# Upstream_Port.net
KiCad netlist of a schematic drawn in Altium Designer
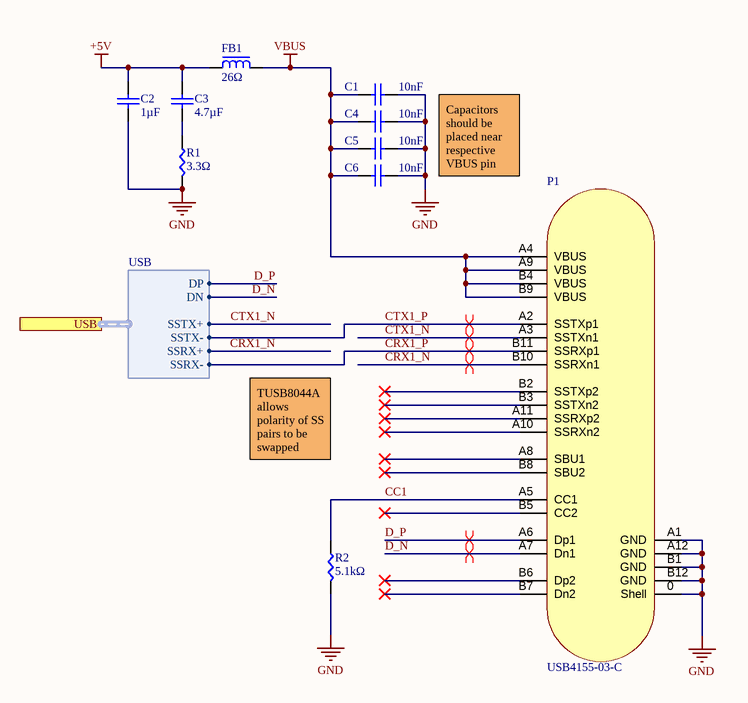
[diagram p0: Upstream_Port.SchDoc]

(export (version "E")
  (design (tool "Eeschema 10.0.6"))
  (components
    (comp (ref "C1")
      (value "10nF")
      (footprint "CAP0402")
      (description "10000 pF ±10% 50V Ceramic Capacitor X7R 0402 (1005 Metric)")
      (fields (field (name "VOLTAGE") "50V") (field (name "Comment") "CC0402KRX7R9BB103"))
      (libsource (lib "Schlib1") (part "CC0402KRX7R9BB103"))
    )
    (comp (ref "C2")
      (value "1µF")
      (footprint "CAP0402")
      (description "1 µF ±10% 50V Ceramic Capacitor X5R 0402 (1005 Metric)")
      (fields (field (name "VOLTAGE") "50V") (field (name "Comment") "GRM155R61H105KE05D"))
      (libsource (lib "Schlib1") (part "GRM155R61H105KE05D"))
    )
    (comp (ref "C3")
      (value "4.7µF")
      (footprint "CAP0603")
      (description "4.7 µF ±10% 25V Ceramic Capacitor X5R 0603 (1608 Metric)")
      (fields (field (name "VOLTAGE") "25V") (field (name "Comment") "GRM188R61E475KE11D"))
      (libsource (lib "Schlib1") (part "GRM188R61E475KE11D"))
    )
    (comp (ref "C4")
      (value "10nF")
      (footprint "CAP0402")
      (description "10000 pF ±10% 50V Ceramic Capacitor X7R 0402 (1005 Metric)")
      (fields (field (name "VOLTAGE") "50V") (field (name "Comment") "CC0402KRX7R9BB103"))
      (libsource (lib "Schlib1") (part "CC0402KRX7R9BB103"))
    )
    (comp (ref "C5")
      (value "10nF")
      (footprint "CAP0402")
      (description "10000 pF ±10% 50V Ceramic Capacitor X7R 0402 (1005 Metric)")
      (fields (field (name "VOLTAGE") "50V") (field (name "Comment") "CC0402KRX7R9BB103"))
      (libsource (lib "Schlib1") (part "CC0402KRX7R9BB103"))
    )
    (comp (ref "C6")
      (value "10nF")
      (footprint "CAP0402")
      (description "10000 pF ±10% 50V Ceramic Capacitor X7R 0402 (1005 Metric)")
      (fields (field (name "VOLTAGE") "50V") (field (name "Comment") "CC0402KRX7R9BB103"))
      (libsource (lib "Schlib1") (part "CC0402KRX7R9BB103"))
    )
    (comp (ref "FB1")
      (value "26Ω")
      (footprint "BLM18SG260TN1D")
      (description "26 Ohms @ 100 MHz 1 Power Line Ferrite Bead 0603 (1608 Metric) 6A 7mOhm")
      (fields (field (name "Comment") "BLM18SG260TN1D"))
      (libsource (lib "Schlib1") (part "BLM18SG260TN1D"))
    )
    (comp (ref "P1")
      (value "USB4155-03-C")
      (footprint "USB4155-03-C")
      (fields (field (name "MANUFACTURER") "GCT") (field (name "VOLTAGE") "48VDC"))
      (libsource (lib "Schlib1") (part "USB4155-03-C"))
    )
    (comp (ref "R1")
      (value "3.3Ω")
      (footprint "RES0402")
      (fields (field (name "Comment") "ESR10EZPJ3R3"))
      (libsource (lib "Schlib1") (part "ESR10EZPJ3R3"))
    )
    (comp (ref "R2")
      (value "5.1kΩ")
      (footprint "RES0402")
      (description "5.1 kOhms ±1% 0.063W, 1/16W Chip Resistor 0402 (1005 Metric) Moisture Resistant Thick Film")
      (fields (field (name "Comment") "RC0402FR-075K1L"))
      (libsource (lib "Schlib1") (part "RC0402FR-075K1L"))
    )
  )
  (nets
    (net (code "2") (name "+5V") (class "Default")
      (node (ref "C2") (pin "2") (pinfunction "2_2") (pintype "passive"))
      (node (ref "C3") (pin "2") (pinfunction "2_2") (pintype "passive"))
      (node (ref "FB1") (pin "1") (pinfunction "1_1") (pintype "passive"))
    )
    (net (code "3") (name "/CC1") (class "Default")
      (node (ref "P1") (pin "A5") (pinfunction "CC1_A5") (pintype "passive"))
      (node (ref "R2") (pin "2") (pinfunction "2_2") (pintype "passive"))
    )
    (net (code "4") (name "/CRX1_N") (class "Default")
      (node (ref "P1") (pin "B10") (pinfunction "SSRXn1_B10") (pintype "passive"))
    )
    (net (code "5") (name "/CRX1_P") (class "Default")
      (node (ref "P1") (pin "B11") (pinfunction "SSRXp1_B11") (pintype "passive"))
    )
    (net (code "6") (name "/CTX1_N") (class "Default")
      (node (ref "P1") (pin "A3") (pinfunction "SSTXn1_A3") (pintype "passive"))
    )
    (net (code "7") (name "/CTX1_P") (class "Default")
      (node (ref "P1") (pin "A2") (pinfunction "SSTXp1_A2") (pintype "passive"))
    )
    (net (code "8") (name "/D_N") (class "Default")
      (node (ref "P1") (pin "A7") (pinfunction "Dn1_A7") (pintype "passive"))
    )
    (net (code "9") (name "/D_P") (class "Default")
      (node (ref "P1") (pin "A6") (pinfunction "Dp1_A6") (pintype "passive"))
    )
    (net (code "11") (name "GND") (class "Default")
      (node (ref "C1") (pin "1") (pinfunction "1_1") (pintype "passive"))
      (node (ref "C2") (pin "1") (pinfunction "1_1") (pintype "passive"))
      (node (ref "C4") (pin "1") (pinfunction "1_1") (pintype "passive"))
      (node (ref "C5") (pin "1") (pinfunction "1_1") (pintype "passive"))
      (node (ref "C6") (pin "1") (pinfunction "1_1") (pintype "passive"))
      (node (ref "P1") (pin "0") (pinfunction "Shell_0") (pintype "passive"))
      (node (ref "P1") (pin "A1") (pinfunction "GND_A1") (pintype "passive"))
      (node (ref "P1") (pin "A12") (pinfunction "GND_A12") (pintype "passive"))
      (node (ref "P1") (pin "B1") (pinfunction "GND_B1") (pintype "passive"))
      (node (ref "P1") (pin "B12") (pinfunction "GND_B12") (pintype "passive"))
      (node (ref "R1") (pin "1") (pinfunction "1_1") (pintype "passive"))
      (node (ref "R2") (pin "1") (pinfunction "1_1") (pintype "passive"))
    )
    (net (code "12") (name "Net-(C3-Pad1)") (class "Default")
      (node (ref "C3") (pin "1") (pinfunction "1_1") (pintype "passive"))
      (node (ref "R1") (pin "2") (pinfunction "2_2") (pintype "passive"))
    )
    (net (code "13") (name "VBUS") (class "Default")
      (node (ref "C1") (pin "2") (pinfunction "2_2") (pintype "passive"))
      (node (ref "C4") (pin "2") (pinfunction "2_2") (pintype "passive"))
      (node (ref "C5") (pin "2") (pinfunction "2_2") (pintype "passive"))
      (node (ref "C6") (pin "2") (pinfunction "2_2") (pintype "passive"))
      (node (ref "FB1") (pin "2") (pinfunction "2_2") (pintype "passive"))
      (node (ref "P1") (pin "A4") (pinfunction "VBUS_A4") (pintype "passive"))
      (node (ref "P1") (pin "A9") (pinfunction "VBUS_A9") (pintype "passive"))
      (node (ref "P1") (pin "B4") (pinfunction "VBUS_B4") (pintype "passive"))
      (node (ref "P1") (pin "B9") (pinfunction "VBUS_B9") (pintype "passive"))
    )
    (net (code "14") (name "unconnected-(P1-CC2-PadB5)") (class "Default")
      (node (ref "P1") (pin "B5") (pinfunction "CC2_B5") (pintype "passive+no_connect"))
    )
    (net (code "15") (name "unconnected-(P1-Dn2-PadB7)") (class "Default")
      (node (ref "P1") (pin "B7") (pinfunction "Dn2_B7") (pintype "passive+no_connect"))
    )
    (net (code "16") (name "unconnected-(P1-Dp2-PadB6)") (class "Default")
      (node (ref "P1") (pin "B6") (pinfunction "Dp2_B6") (pintype "passive+no_connect"))
    )
    (net (code "17") (name "unconnected-(P1-SBU1-PadA8)") (class "Default")
      (node (ref "P1") (pin "A8") (pinfunction "SBU1_A8") (pintype "passive+no_connect"))
    )
    (net (code "18") (name "unconnected-(P1-SBU2-PadB8)") (class "Default")
      (node (ref "P1") (pin "B8") (pinfunction "SBU2_B8") (pintype "passive+no_connect"))
    )
    (net (code "19") (name "unconnected-(P1-SSRXn2-PadA10)") (class "Default")
      (node (ref "P1") (pin "A10") (pinfunction "SSRXn2_A10") (pintype "passive+no_connect"))
    )
    (net (code "20") (name "unconnected-(P1-SSRXp2-PadA11)") (class "Default")
      (node (ref "P1") (pin "A11") (pinfunction "SSRXp2_A11") (pintype "passive+no_connect"))
    )
    (net (code "21") (name "unconnected-(P1-SSTXn2-PadB3)") (class "Default")
      (node (ref "P1") (pin "B3") (pinfunction "SSTXn2_B3") (pintype "passive+no_connect"))
    )
    (net (code "22") (name "unconnected-(P1-SSTXp2-PadB2)") (class "Default")
      (node (ref "P1") (pin "B2") (pinfunction "SSTXp2_B2") (pintype "passive+no_connect"))
    )
  )
)
